# ratopus.net
KiCad netlist of a schematic drawn in Altium Designer
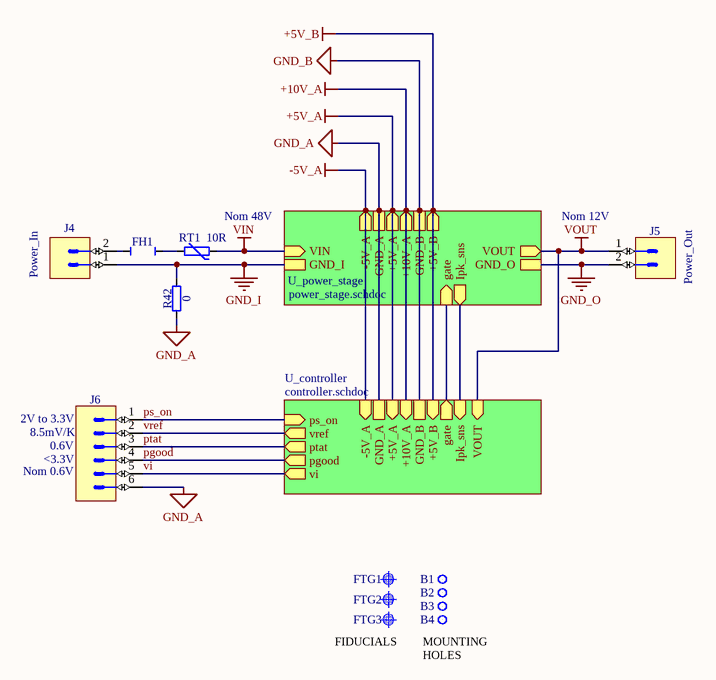
[diagram p0: ratopus.schdoc]

(export (version "E")
  (design (tool "Eeschema 10.0.6"))
  (components
    (comp (ref "B1")
      (value "Non Plated Hole")
      (footprint "MTG270")
      (description "Single Terminal Socket")
      (fields (field (name "PART NUMBER") "NON-PLATED_HOLE2.7") (field (name "AUTHOR") "CERN DEM BC"))
      (libsource (lib "Eletro-mechanical") (part "Single Terminal Socket"))
    )
    (comp (ref "B2")
      (value "Non Plated Hole")
      (footprint "MTG270")
      (description "Single Terminal Socket")
      (fields (field (name "PART NUMBER") "NON-PLATED_HOLE2.7") (field (name "AUTHOR") "CERN DEM BC"))
      (libsource (lib "Eletro-mechanical") (part "Single Terminal Socket"))
    )
    (comp (ref "B3")
      (value "Non Plated Hole")
      (footprint "MTG270")
      (description "Single Terminal Socket")
      (fields (field (name "PART NUMBER") "NON-PLATED_HOLE2.7") (field (name "AUTHOR") "CERN DEM BC"))
      (libsource (lib "Eletro-mechanical") (part "Single Terminal Socket"))
    )
    (comp (ref "B4")
      (value "Non Plated Hole")
      (footprint "MTG270")
      (description "Single Terminal Socket")
      (fields (field (name "PART NUMBER") "NON-PLATED_HOLE2.7") (field (name "AUTHOR") "CERN DEM BC"))
      (libsource (lib "Eletro-mechanical") (part "Single Terminal Socket"))
    )
    (comp (ref "FH1")
      (value "Fuse Holder")
      (footprint "FUSH_SCHURTER_0031.7601")
      (fields
        (field (name "PART NUMBER") "FUSH_SCHURTER_0031.7601")
        (field (name "MANUFACTURER") "SCHURTER")
        (field (name "MANUFACTURER PART NUMBER") "0031.7601")
        (field (name "AUTHOR") "CERN DEM JLC")
      )
      (libsource (lib "Eletro-mechanical") (part "Fuse Holder"))
    )
    (comp (ref "FTG1")
      (value "Use only in PCB")
      (footprint "FIDUCIAL_TOP_C100-200")
      (description "Fiducial Target")
      (fields (field (name "PART NUMBER") "FIDUCIAL_TARGET_C100-200") (field (name "AUTHOR") "CERN DEM JLC"))
      (libsource (lib "Eletro-mechanical") (part "Fiducial Target"))
    )
    (comp (ref "FTG2")
      (value "Use only in PCB")
      (footprint "FIDUCIAL_TOP_C100-200")
      (description "Fiducial Target")
      (fields (field (name "PART NUMBER") "FIDUCIAL_TARGET_C100-200") (field (name "AUTHOR") "CERN DEM JLC"))
      (libsource (lib "Eletro-mechanical") (part "Fiducial Target"))
    )
    (comp (ref "FTG3")
      (value "Use only in PCB")
      (footprint "FIDUCIAL_TOP_C100-200")
      (description "Fiducial Target")
      (fields (field (name "PART NUMBER") "FIDUCIAL_TARGET_C100-200") (field (name "AUTHOR") "CERN DEM JLC"))
      (libsource (lib "Eletro-mechanical") (part "Fiducial Target"))
    )
    (comp (ref "J4")
      (value "~")
      (footprint "PHOENIX_1755736")
      (description "Connector 2 Male")
      (fields
        (field (name "PART NUMBER") "PHOENIX_1755736")
        (field (name "MANUFACTURER") "PHOENIX CONTACT")
        (field (name "AUTHOR") "CERN DEM JLC")
      )
      (libsource (lib "") (part "Connector 2 Male_1"))
    )
    (comp (ref "J5")
      (value "~")
      (footprint "PHOENIX_1755736")
      (description "Connector 2 Male")
      (fields
        (field (name "PART NUMBER") "PHOENIX_1755736")
        (field (name "MANUFACTURER") "PHOENIX CONTACT")
        (field (name "AUTHOR") "CERN DEM JLC")
      )
      (libsource (lib "Connectors") (part "Connector 2 Male"))
    )
    (comp (ref "J6")
      (value "Header 6")
      (footprint "JST_B6B-XH-A(LF)(SN)")
      (description "Connector 6 Male")
      (fields
        (field (name "PART NUMBER") "JST_B6B-XH-A(LF)(SN)")
        (field (name "MANUFACTURER") "JST (JAPAN SOLDERLESS TERMINALS)")
        (field (name "AUTHOR") "CERN DEM JLC")
      )
      (libsource (lib "Connectors") (part "Connector 6 Male"))
    )
    (comp (ref "R42")
      (value "0")
      (footprint "RESC2012X60N")
      (description "Resistor")
      (fields
        (field (name "PART NUMBER") "R0805_0R_JUMPER")
        (field (name "MANUFACTURER") "GENERIC")
        (field (name "AUTHOR") "CERN DEM JLC")
      )
      (libsource (lib "Resistors") (part "Resistor"))
    )
    (comp (ref "RT1")
      (value "10R")
      (footprint "THERM_TDK_B57236S0")
      (description "Thermistor NTC (Negative Temperature Coefficient)")
      (fields
        (field (name "PART NUMBER") "THERM_NTC_10R_TDK_B57236S0100M000")
        (field (name "POWER") "3.5A")
        (field (name "AUTHOR") "CERN DEM JLC")
      )
      (libsource (lib "Resistors") (part "Thermistor NTC"))
    )
  )
  (nets
    (net (code "7") (name "/pgood") (class "Default")
      (node (ref "J6") (pin "4") (pinfunction "4_4") (pintype "bidirectional"))
    )
    (net (code "8") (name "/ps_on") (class "Default")
      (node (ref "J6") (pin "1") (pinfunction "1_1") (pintype "bidirectional"))
    )
    (net (code "9") (name "/ptat") (class "Default")
      (node (ref "J6") (pin "3") (pinfunction "3_3") (pintype "bidirectional"))
    )
    (net (code "10") (name "/vi") (class "Default")
      (node (ref "J6") (pin "5") (pinfunction "5_5") (pintype "bidirectional"))
    )
    (net (code "11") (name "/vref") (class "Default")
      (node (ref "J6") (pin "2") (pinfunction "2_2") (pintype "bidirectional"))
    )
    (net (code "12") (name "GND_A") (class "Default")
      (node (ref "J6") (pin "6") (pinfunction "6_6") (pintype "bidirectional"))
      (node (ref "R42") (pin "1") (pinfunction "1_1") (pintype "passive"))
    )
    (net (code "14") (name "GND_I") (class "Default")
      (node (ref "J4") (pin "1") (pinfunction "1_1") (pintype "bidirectional"))
      (node (ref "R42") (pin "2") (pinfunction "2_2") (pintype "passive"))
    )
    (net (code "15") (name "GND_O") (class "Default")
      (node (ref "J5") (pin "2") (pinfunction "2_2") (pintype "bidirectional"))
    )
    (net (code "16") (name "Net-(FH1-Pad1)") (class "Default")
      (node (ref "FH1") (pin "1") (pinfunction "1_1") (pintype "passive"))
      (node (ref "J4") (pin "2") (pinfunction "2_2") (pintype "bidirectional"))
    )
    (net (code "17") (name "Net-(FH1-Pad2)") (class "Default")
      (node (ref "FH1") (pin "2") (pinfunction "2_2") (pintype "passive"))
      (node (ref "RT1") (pin "1") (pinfunction "1_1") (pintype "passive"))
    )
    (net (code "18") (name "VIN") (class "Default")
      (node (ref "RT1") (pin "2") (pinfunction "2_2") (pintype "passive"))
    )
    (net (code "19") (name "VOUT") (class "Default")
      (node (ref "J5") (pin "1") (pinfunction "1_1") (pintype "bidirectional"))
    )
    (net (code "20") (name "unconnected-(B1-Pad1)") (class "Default")
      (node (ref "B1") (pin "1") (pinfunction "1_1") (pintype "bidirectional"))
    )
    (net (code "21") (name "unconnected-(B2-Pad1)") (class "Default")
      (node (ref "B2") (pin "1") (pinfunction "1_1") (pintype "bidirectional"))
    )
    (net (code "22") (name "unconnected-(B3-Pad1)") (class "Default")
      (node (ref "B3") (pin "1") (pinfunction "1_1") (pintype "bidirectional"))
    )
    (net (code "23") (name "unconnected-(B4-Pad1)") (class "Default")
      (node (ref "B4") (pin "1") (pinfunction "1_1") (pintype "bidirectional"))
    )
  )
)
